# Power.net
KiCad netlist of a schematic drawn in Altium Designer
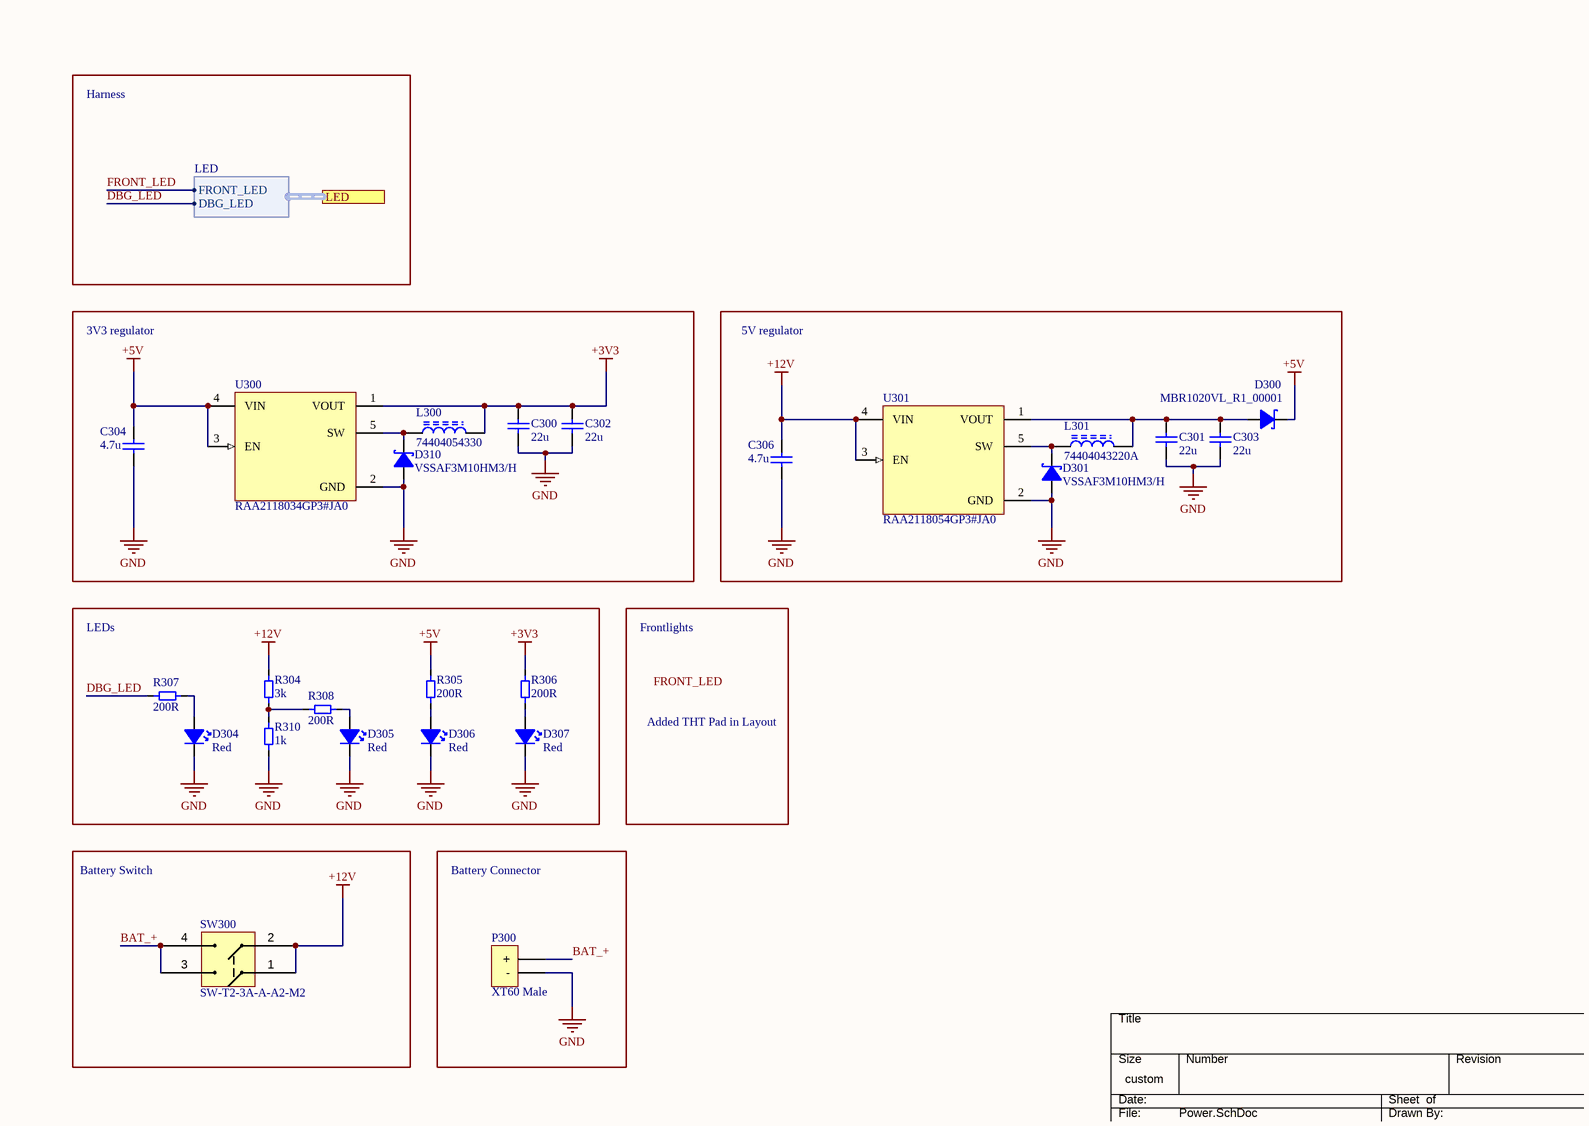
[diagram p0: Power.SchDoc]

(export (version "E")
  (design (tool "Eeschema 10.0.6"))
  (components
    (comp (ref "C300")
      (value "22u")
      (footprint "MLCC_0603_M")
      (description "MLCC, 0603, 22u, 10%, 16V, X5R")
      (fields (field (name "TOLERANCE") "10%") (field (name "MANUFACTURER") "Any"))
      (libsource (lib "Krakul Vault") (part "CAPACITOR_NONPOL_IEC"))
    )
    (comp (ref "C301")
      (value "22u")
      (footprint "MLCC_0603_M")
      (description "MLCC, 0603, 22u, 10%, 16V, X5R")
      (fields (field (name "TOLERANCE") "10%") (field (name "MANUFACTURER") "Any"))
      (libsource (lib "Krakul Vault") (part "CAPACITOR_NONPOL_IEC"))
    )
    (comp (ref "C302")
      (value "22u")
      (footprint "MLCC_0603_M")
      (description "MLCC, 0603, 22u, 10%, 16V, X5R")
      (fields (field (name "TOLERANCE") "10%") (field (name "MANUFACTURER") "Any"))
      (libsource (lib "Krakul Vault") (part "CAPACITOR_NONPOL_IEC"))
    )
    (comp (ref "C303")
      (value "22u")
      (footprint "MLCC_0603_M")
      (description "MLCC, 0603, 22u, 10%, 16V, X5R")
      (fields (field (name "TOLERANCE") "10%") (field (name "MANUFACTURER") "Any"))
      (libsource (lib "Krakul Vault") (part "CAPACITOR_NONPOL_IEC"))
    )
    (comp (ref "C304")
      (value "4.7u")
      (footprint "MLCC_1206_M")
      (description "MLCC, 1206, 4.7u, 10%, 35V, X5R")
      (fields (field (name "VOLTAGE") "35V") (field (name "TOLERANCE") "10%"))
      (libsource (lib "Krakul Vault") (part "CAPACITOR_NONPOL_IEC"))
    )
    (comp (ref "C306")
      (value "4.7u")
      (footprint "MLCC_1206_M")
      (description "MLCC, 1206, 4.7u, 10%, 35V, X5R")
      (fields (field (name "VOLTAGE") "35V") (field (name "TOLERANCE") "10%"))
      (libsource (lib "Krakul Vault") (part "CAPACITOR_NONPOL_IEC"))
    )
    (comp (ref "D300")
      (value "MBR1020VL_R1_00001")
      (footprint "FP-MBR1020VL_R1_00001-MFG")
      (description "Rectifier Diode, Schottky, 1 Phase, 1 Element, 1A, 20V V(RRM), Silicon")
      (fields (field (name "MANUFACTURER") "Panjit"))
      (libsource (lib "Krakul Vault") (part "Schottky generic 2 pins"))
    )
    (comp (ref "D301")
      (value "VSSAF3M10HM3/H")
      (footprint "VSSAF3M10HM3_H-Footprint-1")
      (description "Rectifier Diode, Schottky, 1 Phase, 1 Element, 2.3A, 100V V(RRM), Silicon, DO-221AC")
      (libsource (lib "Krakul Vault") (part "Schottky generic 2 pins"))
    )
    (comp (ref "D304")
      (value "Red")
      (footprint "0603 RED LED")
      (description "Generic red 0603 LED")
      (fields (field (name "PART NUMBER") "Any Red 0603 LED") (field (name "MANUFACTURER") "Any"))
      (libsource (lib "Krakul Vault") (part "LED generic"))
    )
    (comp (ref "D305")
      (value "Red")
      (footprint "0603 RED LED")
      (description "Generic red 0603 LED")
      (fields (field (name "PART NUMBER") "Any Red 0603 LED") (field (name "MANUFACTURER") "Any"))
      (libsource (lib "Krakul Vault") (part "LED generic"))
    )
    (comp (ref "D306")
      (value "Red")
      (footprint "0603 RED LED")
      (description "Generic red 0603 LED")
      (fields (field (name "PART NUMBER") "Any Red 0603 LED") (field (name "MANUFACTURER") "Any"))
      (libsource (lib "Krakul Vault") (part "LED generic"))
    )
    (comp (ref "D307")
      (value "Red")
      (footprint "0603 RED LED")
      (description "Generic red 0603 LED")
      (fields (field (name "PART NUMBER") "Any Red 0603 LED") (field (name "MANUFACTURER") "Any"))
      (libsource (lib "Krakul Vault") (part "LED generic"))
    )
    (comp (ref "D310")
      (value "VSSAF3M10HM3/H")
      (footprint "VSSAF3M10HM3_H-Footprint-1")
      (description "Rectifier Diode, Schottky, 1 Phase, 1 Element, 2.3A, 100V V(RRM), Silicon, DO-221AC")
      (libsource (lib "Krakul Vault") (part "Schottky generic 2 pins"))
    )
    (comp (ref "L300")
      (value "74404054330")
      (footprint "WE-LQS_5040")
      (description "Inductor Power Semi-Shielded Wirewound 33uH 20% 100KHz 1.2A 0.188Ohm DCR 2020 Automotive T/R")
      (fields (field (name "MANUFACTURER") "Wurth Elektronik") (field (name "PART NUMBER") "74404043220A"))
      (libsource (lib "Krakul Vault") (part "INDUCTOR_SHIELDED"))
    )
    (comp (ref "L301")
      (value "74404043220A")
      (footprint "WE-LQS_4025")
      (description "General Purpose Inductor, 22uH, 20%, 1 Element, Nickel-zinc Ferrite-Core, SMD, 1616")
      (fields (field (name "MANUFACTURER") "Wurth Elektronik"))
      (libsource (lib "Krakul Vault") (part "INDUCTOR_SHIELDED"))
    )
    (comp (ref "P300")
      (value "XT60 Male")
      (footprint "XT60 male TH")
      (fields (field (name "MANUFACTURER") "DFRobot") (field (name "PART NUMBER") "1738-1437-ND"))
      (libsource (lib "Krakul Vault") (part "XT60"))
    )
    (comp (ref "R304")
      (value "3k")
      (footprint "Resistor_0603_M")
      (description "Resistor, 0603, 3k, 1%, 1/10W")
      (fields (field (name "MANUFACTURER") "Any") (field (name "TOLERANCE") "1%"))
      (libsource (lib "Krakul Vault") (part "RESISTOR_GENERIC_IEC"))
    )
    (comp (ref "R305")
      (value "200R")
      (footprint "Resistor_0603_M")
      (description "Resistor, 0603, 200R, 1%, 1/10W")
      (fields (field (name "TOLERANCE") "1%") (field (name "POWER") "100mW"))
      (libsource (lib "Krakul Vault") (part "RESISTOR_GENERIC_IEC"))
    )
    (comp (ref "R306")
      (value "200R")
      (footprint "Resistor_0603_M")
      (description "Resistor, 0603, 200R, 1%, 1/10W")
      (fields (field (name "TOLERANCE") "1%") (field (name "POWER") "100mW"))
      (libsource (lib "Krakul Vault") (part "RESISTOR_GENERIC_IEC"))
    )
    (comp (ref "R307")
      (value "200R")
      (footprint "Resistor_0603_M")
      (description "Resistor, 0603, 200R, 1%, 1/10W")
      (fields (field (name "TOLERANCE") "1%") (field (name "POWER") "100mW"))
      (libsource (lib "Krakul Vault") (part "RESISTOR_GENERIC_IEC"))
    )
    (comp (ref "R308")
      (value "200R")
      (footprint "Resistor_0603_M")
      (description "Resistor, 0603, 200R, 1%, 1/10W")
      (fields (field (name "TOLERANCE") "1%") (field (name "POWER") "100mW"))
      (libsource (lib "Krakul Vault") (part "RESISTOR_GENERIC_IEC"))
    )
    (comp (ref "R310")
      (value "1k")
      (footprint "Resistor_0603_M")
      (description "Resistor, 0603, 1k, 0.1%, 1/16W")
      (fields (field (name "MANUFACTURER") "Any"))
      (libsource (lib "Krakul Vault") (part "RESISTOR_GENERIC_IEC"))
    )
    (comp (ref "SW300")
      (value "SW-T2-3A-A-A2-M2")
      (footprint "SW-T2-3A-A-A2-M2")
      (description "Toggle Switch, Miniature, Solder, DPST, On-off")
      (fields (field (name "MANUFACTURER") "Adam Tech"))
      (libsource (lib "Krakul Vault") (part "DPST"))
    )
    (comp (ref "U300")
      (value "RAA2118034GP3#JA0")
      (footprint "P5_064B_MFG")
      (description "Switching Regulator, Current-mode, 0.3A, 170kHz Switching Freq-Max, PDSO5")
      (fields (field (name "MANUFACTURER") "Renesas / Intersil"))
      (libsource (lib "Krakul Vault") (part "RAA2118034GP3#JA0"))
    )
    (comp (ref "U301")
      (value "RAA2118054GP3#JA0")
      (footprint "P5_064B_MFG")
      (description "Switching Regulator, Current-mode, 0.3A, 230kHz Switching Freq-Max, PDSO5")
      (fields (field (name "MANUFACTURER") "Renesas / Intersil"))
      (libsource (lib "Krakul Vault") (part "04ef17e7ed04f306c00cc4b237f44d7"))
    )
  )
  (nets
    (net (code "2") (name "+3V3") (class "Default")
      (node (ref "C300") (pin "2") (pinfunction "2_2") (pintype "passive"))
      (node (ref "C302") (pin "2") (pinfunction "2_2") (pintype "passive"))
      (node (ref "L300") (pin "2") (pinfunction "2_2") (pintype "passive"))
      (node (ref "R306") (pin "1") (pinfunction "1_1") (pintype "passive"))
      (node (ref "U300") (pin "1") (pinfunction "VOUT_1") (pintype "power_in"))
    )
    (net (code "3") (name "+5V") (class "Default")
      (node (ref "C304") (pin "2") (pinfunction "2_2") (pintype "passive"))
      (node (ref "D300") (pin "1") (pinfunction "C_1") (pintype "passive"))
      (node (ref "R305") (pin "1") (pinfunction "1_1") (pintype "passive"))
      (node (ref "U300") (pin "3") (pinfunction "EN_3") (pintype "input"))
      (node (ref "U300") (pin "4") (pinfunction "VIN_4") (pintype "power_in"))
    )
    (net (code "4") (name "+12V") (class "Default")
      (node (ref "C306") (pin "2") (pinfunction "2_2") (pintype "passive"))
      (node (ref "R304") (pin "2") (pinfunction "2_2") (pintype "passive"))
      (node (ref "SW300") (pin "1") (pinfunction "1_1") (pintype "passive"))
      (node (ref "SW300") (pin "2") (pinfunction "2_2") (pintype "passive"))
      (node (ref "U301") (pin "3") (pinfunction "EN_3") (pintype "input"))
      (node (ref "U301") (pin "4") (pinfunction "VIN_4") (pintype "power_in"))
    )
    (net (code "5") (name "/BAT_+") (class "Default")
      (node (ref "P300") (pin "+") (pinfunction "+_+") (pintype "passive"))
      (node (ref "SW300") (pin "3") (pinfunction "3_3") (pintype "passive"))
      (node (ref "SW300") (pin "4") (pinfunction "4_4") (pintype "passive"))
    )
    (net (code "6") (name "/DBG_LED") (class "Default")
      (node (ref "R307") (pin "1") (pinfunction "1_1") (pintype "passive"))
    )
    (net (code "9") (name "GND") (class "Default")
      (node (ref "C300") (pin "1") (pinfunction "1_1") (pintype "passive"))
      (node (ref "C301") (pin "1") (pinfunction "1_1") (pintype "passive"))
      (node (ref "C302") (pin "1") (pinfunction "1_1") (pintype "passive"))
      (node (ref "C303") (pin "1") (pinfunction "1_1") (pintype "passive"))
      (node (ref "C304") (pin "1") (pinfunction "1_1") (pintype "passive"))
      (node (ref "C306") (pin "1") (pinfunction "1_1") (pintype "passive"))
      (node (ref "D301") (pin "2") (pinfunction "A_2") (pintype "passive"))
      (node (ref "D304") (pin "1") (pinfunction "C_1") (pintype "passive"))
      (node (ref "D305") (pin "1") (pinfunction "C_1") (pintype "passive"))
      (node (ref "D306") (pin "1") (pinfunction "C_1") (pintype "passive"))
      (node (ref "D307") (pin "1") (pinfunction "C_1") (pintype "passive"))
      (node (ref "D310") (pin "2") (pinfunction "A_2") (pintype "passive"))
      (node (ref "P300") (pin "-") (pinfunction "-_-") (pintype "passive"))
      (node (ref "R310") (pin "1") (pinfunction "1_1") (pintype "passive"))
      (node (ref "U300") (pin "2") (pinfunction "GND_2") (pintype "power_in"))
      (node (ref "U301") (pin "2") (pinfunction "GND_2") (pintype "power_in"))
    )
    (net (code "10") (name "Net-(D300-A)") (class "Default")
      (node (ref "C301") (pin "2") (pinfunction "2_2") (pintype "passive"))
      (node (ref "C303") (pin "2") (pinfunction "2_2") (pintype "passive"))
      (node (ref "D300") (pin "2") (pinfunction "A_2") (pintype "passive"))
      (node (ref "L301") (pin "2") (pinfunction "2_2") (pintype "passive"))
      (node (ref "U301") (pin "1") (pinfunction "VOUT_1") (pintype "power_in"))
    )
    (net (code "11") (name "Net-(D301-C)") (class "Default")
      (node (ref "D301") (pin "1") (pinfunction "C_1") (pintype "passive"))
      (node (ref "L301") (pin "1") (pinfunction "1_1") (pintype "passive"))
      (node (ref "U301") (pin "5") (pinfunction "SW_5") (pintype "passive"))
    )
    (net (code "12") (name "Net-(D304-A)") (class "Default")
      (node (ref "D304") (pin "2") (pinfunction "A_2") (pintype "passive"))
      (node (ref "R307") (pin "2") (pinfunction "2_2") (pintype "passive"))
    )
    (net (code "13") (name "Net-(D305-A)") (class "Default")
      (node (ref "D305") (pin "2") (pinfunction "A_2") (pintype "passive"))
      (node (ref "R308") (pin "2") (pinfunction "2_2") (pintype "passive"))
    )
    (net (code "14") (name "Net-(D306-A)") (class "Default")
      (node (ref "D306") (pin "2") (pinfunction "A_2") (pintype "passive"))
      (node (ref "R305") (pin "2") (pinfunction "2_2") (pintype "passive"))
    )
    (net (code "15") (name "Net-(D307-A)") (class "Default")
      (node (ref "D307") (pin "2") (pinfunction "A_2") (pintype "passive"))
      (node (ref "R306") (pin "2") (pinfunction "2_2") (pintype "passive"))
    )
    (net (code "16") (name "Net-(D310-C)") (class "Default")
      (node (ref "D310") (pin "1") (pinfunction "C_1") (pintype "passive"))
      (node (ref "L300") (pin "1") (pinfunction "1_1") (pintype "passive"))
      (node (ref "U300") (pin "5") (pinfunction "SW_5") (pintype "passive"))
    )
    (net (code "17") (name "Net-(R304-Pad1)") (class "Default")
      (node (ref "R304") (pin "1") (pinfunction "1_1") (pintype "passive"))
      (node (ref "R308") (pin "1") (pinfunction "1_1") (pintype "passive"))
      (node (ref "R310") (pin "2") (pinfunction "2_2") (pintype "passive"))
    )
  )
)
